# 2_PWR_schdoc.net
KiCad netlist of a schematic drawn in Altium Designer
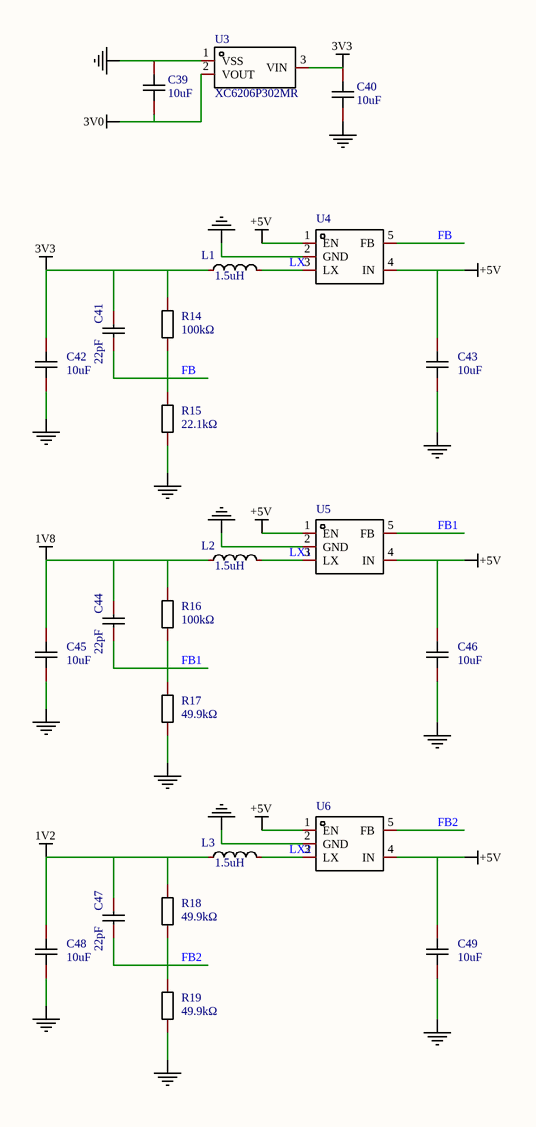
[diagram p0: 2_PWR.schdoc.schdoc]

(export (version "E")
  (design (tool "Eeschema 10.0.6"))
  (components
    (comp (ref "C39")
      (value "10uF")
      (fields
        (field (name "NAME") "10uF")
        (field (name "MANUFACTURER") "SAMSUNG(三星)")
        (field (name "MANUFACTURER PART") "CL10A106KP8NNNC")
        (field (name "TOLERANCE") "±10%")
      )
      (libsource (lib "altium-import") (part "root_1_CL10A106KP8NNNC_"))
    )
    (comp (ref "C40")
      (value "10uF")
      (fields
        (field (name "NAME") "10uF")
        (field (name "MANUFACTURER") "SAMSUNG(三星)")
        (field (name "MANUFACTURER PART") "CL10A106KP8NNNC")
        (field (name "TOLERANCE") "±10%")
      )
      (libsource (lib "altium-import") (part "root_1_CL10A106KP8NNNC_"))
    )
    (comp (ref "C41")
      (value "22pF")
      (fields
        (field (name "MANUFACTURER PART") "CL10C220JB8NNNC")
        (field (name "MANUFACTURER") "SAMSUNG(三星)")
        (field (name "TOLERANCE") "±5%")
      )
      (libsource (lib "altium-import") (part "root_1_CL10C220JB8NNNC_"))
    )
    (comp (ref "C42")
      (value "10uF")
      (fields
        (field (name "NAME") "10uF")
        (field (name "MANUFACTURER") "SAMSUNG(三星)")
        (field (name "MANUFACTURER PART") "CL10A106KP8NNNC")
        (field (name "TOLERANCE") "±10%")
      )
      (libsource (lib "altium-import") (part "root_1_CL10A106KP8NNNC_"))
    )
    (comp (ref "C43")
      (value "10uF")
      (fields
        (field (name "NAME") "10uF")
        (field (name "MANUFACTURER") "SAMSUNG(三星)")
        (field (name "MANUFACTURER PART") "CL10A106KP8NNNC")
        (field (name "TOLERANCE") "±10%")
      )
      (libsource (lib "altium-import") (part "root_1_CL10A106KP8NNNC_"))
    )
    (comp (ref "C44")
      (value "22pF")
      (fields
        (field (name "MANUFACTURER PART") "CL10C220JB8NNNC")
        (field (name "MANUFACTURER") "SAMSUNG(三星)")
        (field (name "TOLERANCE") "±5%")
      )
      (libsource (lib "altium-import") (part "root_1_CL10C220JB8NNNC_"))
    )
    (comp (ref "C45")
      (value "10uF")
      (fields
        (field (name "NAME") "10uF")
        (field (name "MANUFACTURER") "SAMSUNG(三星)")
        (field (name "MANUFACTURER PART") "CL10A106KP8NNNC")
        (field (name "TOLERANCE") "±10%")
      )
      (libsource (lib "altium-import") (part "root_1_CL10A106KP8NNNC_"))
    )
    (comp (ref "C46")
      (value "10uF")
      (fields
        (field (name "NAME") "10uF")
        (field (name "MANUFACTURER") "SAMSUNG(三星)")
        (field (name "MANUFACTURER PART") "CL10A106KP8NNNC")
        (field (name "TOLERANCE") "±10%")
      )
      (libsource (lib "altium-import") (part "root_1_CL10A106KP8NNNC_"))
    )
    (comp (ref "C47")
      (value "22pF")
      (fields
        (field (name "MANUFACTURER PART") "CL10C220JB8NNNC")
        (field (name "MANUFACTURER") "SAMSUNG(三星)")
        (field (name "TOLERANCE") "±5%")
      )
      (libsource (lib "altium-import") (part "root_1_CL10C220JB8NNNC_"))
    )
    (comp (ref "C48")
      (value "10uF")
      (fields
        (field (name "NAME") "10uF")
        (field (name "MANUFACTURER") "SAMSUNG(三星)")
        (field (name "MANUFACTURER PART") "CL10A106KP8NNNC")
        (field (name "TOLERANCE") "±10%")
      )
      (libsource (lib "altium-import") (part "root_1_CL10A106KP8NNNC_"))
    )
    (comp (ref "C49")
      (value "10uF")
      (fields
        (field (name "NAME") "10uF")
        (field (name "MANUFACTURER") "SAMSUNG(三星)")
        (field (name "MANUFACTURER PART") "CL10A106KP8NNNC")
        (field (name "TOLERANCE") "±10%")
      )
      (libsource (lib "altium-import") (part "root_1_CL10A106KP8NNNC_"))
    )
    (comp (ref "L1")
      (value "1.5uH")
      (fields
        (field (name "NAME") "1.5uH")
        (field (name "MANUFACTURER") "FH(风华)")
        (field (name "MANUFACTURER PART") "PIM252010-1R5MTS00")
        (field (name "TOLERANCE") "±20%")
      )
      (libsource (lib "altium-import") (part "root_0_PIM252010-1R5MTS00_"))
    )
    (comp (ref "L2")
      (value "1.5uH")
      (fields
        (field (name "NAME") "1.5uH")
        (field (name "MANUFACTURER") "FH(风华)")
        (field (name "MANUFACTURER PART") "PIM252010-1R5MTS00")
        (field (name "TOLERANCE") "±20%")
      )
      (libsource (lib "altium-import") (part "root_0_PIM252010-1R5MTS00_"))
    )
    (comp (ref "L3")
      (value "1.5uH")
      (fields
        (field (name "NAME") "1.5uH")
        (field (name "MANUFACTURER") "FH(风华)")
        (field (name "MANUFACTURER PART") "PIM252010-1R5MTS00")
        (field (name "TOLERANCE") "±20%")
      )
      (libsource (lib "altium-import") (part "root_0_PIM252010-1R5MTS00_"))
    )
    (comp (ref "R14")
      (value "100kΩ")
      (fields
        (field (name "NAME") "100kΩ")
        (field (name "MANUFACTURER") "UNI-ROYAL(厚声)")
        (field (name "MANUFACTURER PART") "0603WAF1003T5E")
        (field (name "TOLERANCE") "±1%")
      )
      (libsource (lib "altium-import") (part "root_1_0603WAF1003T5E_"))
    )
    (comp (ref "R15")
      (value "22.1kΩ")
      (fields
        (field (name "NAME") "22.1kΩ")
        (field (name "MANUFACTURER") "UNI-ROYAL(厚声)")
        (field (name "MANUFACTURER PART") "0603WAF2212T5E")
        (field (name "TOLERANCE") "±1%")
      )
      (libsource (lib "altium-import") (part "root_1_0603WAF2212T5E_"))
    )
    (comp (ref "R16")
      (value "100kΩ")
      (fields
        (field (name "NAME") "100kΩ")
        (field (name "MANUFACTURER") "UNI-ROYAL(厚声)")
        (field (name "MANUFACTURER PART") "0603WAF1003T5E")
        (field (name "TOLERANCE") "±1%")
      )
      (libsource (lib "altium-import") (part "root_1_0603WAF1003T5E_"))
    )
    (comp (ref "R17")
      (value "49.9kΩ")
      (fields
        (field (name "NAME") "49.9kΩ")
        (field (name "MANUFACTURER") "UNI-ROYAL(厚声)")
        (field (name "MANUFACTURER PART") "0603WAF4992T5E")
        (field (name "TOLERANCE") "±1%")
      )
      (libsource (lib "altium-import") (part "root_1_0603WAF4992T5E_"))
    )
    (comp (ref "R18")
      (value "49.9kΩ")
      (fields
        (field (name "NAME") "49.9kΩ")
        (field (name "MANUFACTURER") "UNI-ROYAL(厚声)")
        (field (name "MANUFACTURER PART") "0603WAF4992T5E")
        (field (name "TOLERANCE") "±1%")
      )
      (libsource (lib "altium-import") (part "root_1_0603WAF4992T5E_"))
    )
    (comp (ref "R19")
      (value "49.9kΩ")
      (fields
        (field (name "NAME") "49.9kΩ")
        (field (name "MANUFACTURER") "UNI-ROYAL(厚声)")
        (field (name "MANUFACTURER PART") "0603WAF4992T5E")
        (field (name "TOLERANCE") "±1%")
      )
      (libsource (lib "altium-import") (part "root_1_0603WAF4992T5E_"))
    )
    (comp (ref "U3")
      (value "XC6206P302MR")
      (description "输出类型:固定;输出极性:正;最大输入电压:8V;输出电压:3V;输出电流:250mA;电源纹波抑制比(PSRR):40dB@(1kHz);")
      (fields (field (name "NAME") "XC6206P302MR") (field (name "MANUFACTURER") "UMW(友台半导体)"))
      (libsource (lib "altium-import") (part "root_0_XC6206P302MR_C347375_"))
    )
    (comp (ref "U4")
      (value "SY8089A1AAC")
      (fields (field (name "MANUFACTURER") "silergy(矽力杰)"))
      (libsource (lib "altium-import") (part "root_0_SY8089A1AAC_"))
    )
    (comp (ref "U5")
      (value "SY8089A1AAC")
      (fields (field (name "MANUFACTURER") "silergy(矽力杰)"))
      (libsource (lib "altium-import") (part "root_0_SY8089A1AAC_"))
    )
    (comp (ref "U6")
      (value "SY8089A1AAC")
      (fields (field (name "MANUFACTURER") "silergy(矽力杰)"))
      (libsource (lib "altium-import") (part "root_0_SY8089A1AAC_"))
    )
  )
  (nets
    (net (code "1") (name "+5V") (class "Default")
      (node (ref "C43") (pin "2") (pinfunction "2_2") (pintype "passive"))
      (node (ref "C46") (pin "2") (pinfunction "2_2") (pintype "passive"))
      (node (ref "C49") (pin "2") (pinfunction "2_2") (pintype "passive"))
      (node (ref "U4") (pin "1") (pinfunction "EN_1") (pintype "passive"))
      (node (ref "U4") (pin "4") (pinfunction "IN_4") (pintype "passive"))
      (node (ref "U5") (pin "1") (pinfunction "EN_1") (pintype "passive"))
      (node (ref "U5") (pin "4") (pinfunction "IN_4") (pintype "passive"))
      (node (ref "U6") (pin "1") (pinfunction "EN_1") (pintype "passive"))
      (node (ref "U6") (pin "4") (pinfunction "IN_4") (pintype "passive"))
    )
    (net (code "2") (name "/FB") (class "Default")
      (node (ref "C41") (pin "1") (pinfunction "1_1") (pintype "passive"))
      (node (ref "R14") (pin "1") (pinfunction "1_1") (pintype "passive"))
      (node (ref "R15") (pin "2") (pinfunction "2_2") (pintype "passive"))
      (node (ref "U4") (pin "5") (pinfunction "FB_5") (pintype "passive"))
    )
    (net (code "3") (name "/FB1") (class "Default")
      (node (ref "C44") (pin "1") (pinfunction "1_1") (pintype "passive"))
      (node (ref "R16") (pin "1") (pinfunction "1_1") (pintype "passive"))
      (node (ref "R17") (pin "2") (pinfunction "2_2") (pintype "passive"))
      (node (ref "U5") (pin "5") (pinfunction "FB_5") (pintype "passive"))
    )
    (net (code "4") (name "/FB2") (class "Default")
      (node (ref "C47") (pin "1") (pinfunction "1_1") (pintype "passive"))
      (node (ref "R18") (pin "1") (pinfunction "1_1") (pintype "passive"))
      (node (ref "R19") (pin "2") (pinfunction "2_2") (pintype "passive"))
      (node (ref "U6") (pin "5") (pinfunction "FB_5") (pintype "passive"))
    )
    (net (code "5") (name "/LX") (class "Default")
      (node (ref "L1") (pin "2") (pinfunction "2_2") (pintype "passive"))
      (node (ref "U4") (pin "3") (pinfunction "LX_3") (pintype "passive"))
    )
    (net (code "6") (name "/LX1") (class "Default")
      (node (ref "L2") (pin "2") (pinfunction "2_2") (pintype "passive"))
      (node (ref "U5") (pin "3") (pinfunction "LX_3") (pintype "passive"))
    )
    (net (code "7") (name "/LX2") (class "Default")
      (node (ref "L3") (pin "2") (pinfunction "2_2") (pintype "passive"))
      (node (ref "U6") (pin "3") (pinfunction "LX_3") (pintype "passive"))
    )
    (net (code "8") (name "1V2") (class "Default")
      (node (ref "C47") (pin "2") (pinfunction "2_2") (pintype "passive"))
      (node (ref "C48") (pin "2") (pinfunction "2_2") (pintype "passive"))
      (node (ref "L3") (pin "1") (pinfunction "1_1") (pintype "passive"))
      (node (ref "R18") (pin "2") (pinfunction "2_2") (pintype "passive"))
    )
    (net (code "9") (name "1V8") (class "Default")
      (node (ref "C44") (pin "2") (pinfunction "2_2") (pintype "passive"))
      (node (ref "C45") (pin "2") (pinfunction "2_2") (pintype "passive"))
      (node (ref "L2") (pin "1") (pinfunction "1_1") (pintype "passive"))
      (node (ref "R16") (pin "2") (pinfunction "2_2") (pintype "passive"))
    )
    (net (code "10") (name "3V0") (class "Default")
      (node (ref "C39") (pin "1") (pinfunction "1_1") (pintype "passive"))
      (node (ref "U3") (pin "2") (pinfunction "VOUT_2") (pintype "passive"))
    )
    (net (code "11") (name "3V3") (class "Default")
      (node (ref "C40") (pin "2") (pinfunction "2_2") (pintype "passive"))
      (node (ref "C41") (pin "2") (pinfunction "2_2") (pintype "passive"))
      (node (ref "C42") (pin "2") (pinfunction "2_2") (pintype "passive"))
      (node (ref "L1") (pin "1") (pinfunction "1_1") (pintype "passive"))
      (node (ref "R14") (pin "2") (pinfunction "2_2") (pintype "passive"))
      (node (ref "U3") (pin "3") (pinfunction "VIN_3") (pintype "passive"))
    )
    (net (code "12") (name "<NO NET>") (class "Default")
      (node (ref "C39") (pin "2") (pinfunction "2_2") (pintype "passive"))
      (node (ref "C40") (pin "1") (pinfunction "1_1") (pintype "passive"))
      (node (ref "U3") (pin "1") (pinfunction "VSS_1") (pintype "passive"))
    )
    (net (code "13") (name "GND") (class "Default")
      (node (ref "C42") (pin "1") (pinfunction "1_1") (pintype "passive"))
      (node (ref "C43") (pin "1") (pinfunction "1_1") (pintype "passive"))
      (node (ref "C45") (pin "1") (pinfunction "1_1") (pintype "passive"))
      (node (ref "C46") (pin "1") (pinfunction "1_1") (pintype "passive"))
      (node (ref "C48") (pin "1") (pinfunction "1_1") (pintype "passive"))
      (node (ref "C49") (pin "1") (pinfunction "1_1") (pintype "passive"))
      (node (ref "R15") (pin "1") (pinfunction "1_1") (pintype "passive"))
      (node (ref "R17") (pin "1") (pinfunction "1_1") (pintype "passive"))
      (node (ref "R19") (pin "1") (pinfunction "1_1") (pintype "passive"))
      (node (ref "U4") (pin "2") (pinfunction "GND_2") (pintype "passive"))
      (node (ref "U5") (pin "2") (pinfunction "GND_2") (pintype "passive"))
      (node (ref "U6") (pin "2") (pinfunction "GND_2") (pintype "passive"))
    )
  )
)
